# ESP01_Breakout.net
KiCad netlist of a schematic drawn in EAGLE
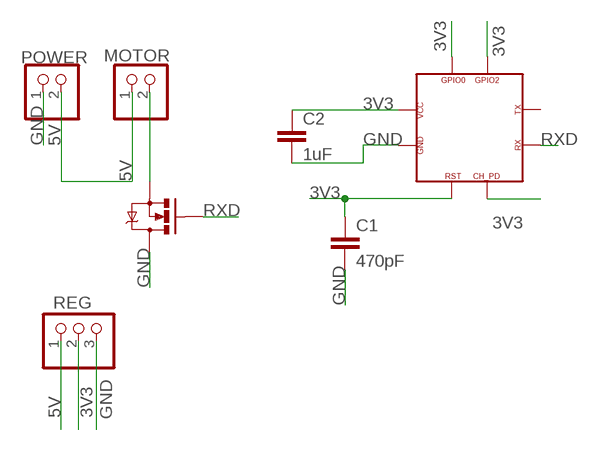
[diagram p0: schematic, sheet 1]

(export (version "E")
  (design (tool "Eeschema 10.0.6"))
  (components
    (comp (ref "C1")
      (value "470pF")
      (footprint "eagle-import:CAP-PTH-SMALLEZ")
      (libsource (lib "eagle-import") (part "CAPEZ"))
    )
    (comp (ref "C2")
      (value "1uF")
      (footprint "eagle-import:CAP-PTH-SMALLEZ")
      (libsource (lib "eagle-import") (part "CAPEZ"))
    )
    (comp (ref "MOTOR")
      (value "PINHD-1X2/90")
      (footprint "eagle-import:1X02_90")
      (libsource (lib "eagle-import") (part "PINHD-1X2/90"))
    )
    (comp (ref "POWER")
      (value "PINHD-1X2/90")
      (footprint "eagle-import:1X02_90")
      (libsource (lib "eagle-import") (part "PINHD-1X2/90"))
    )
    (comp (ref "Q1")
      (value "MOSFET-NCHANNEL2N7000")
      (footprint "eagle-import:TO-92")
      (libsource (lib "eagle-import") (part "MOSFET-NCHANNEL2N7000"))
    )
    (comp (ref "REG")
      (value "PINHD-1X3")
      (footprint "eagle-import:1X03")
      (libsource (lib "eagle-import") (part "PINHD-1X3"))
    )
    (comp (ref "U$2")
      (value "ESP-01")
      (footprint "eagle-import:ESP-01")
      (libsource (lib "eagle-import") (part "ESP-01"))
    )
  )
  (nets
    (net (code "1") (name "/3V3") (class "Default")
      (node (ref "C1") (pin "1") (pinfunction "1_1") (pintype "passive"))
      (node (ref "C2") (pin "1") (pinfunction "1_1") (pintype "passive"))
      (node (ref "REG") (pin "2") (pinfunction "2_2") (pintype "passive"))
      (node (ref "U$2") (pin "CH_PD") (pinfunction "CP_PD_CH_PD") (pintype "bidirectional"))
      (node (ref "U$2") (pin "GPIO0") (pinfunction "GPIO0_GPIO0") (pintype "bidirectional"))
      (node (ref "U$2") (pin "GPIO2") (pinfunction "GPIO2_GPIO2") (pintype "bidirectional"))
      (node (ref "U$2") (pin "RST") (pinfunction "RST_RST") (pintype "bidirectional"))
      (node (ref "U$2") (pin "VCC") (pinfunction "VCC_VCC") (pintype "bidirectional"))
    )
    (net (code "2") (name "/5V") (class "Default")
      (node (ref "MOTOR") (pin "1") (pinfunction "1_1") (pintype "passive"))
      (node (ref "POWER") (pin "2") (pinfunction "2_2") (pintype "passive"))
      (node (ref "REG") (pin "1") (pinfunction "1_1") (pintype "passive"))
    )
    (net (code "3") (name "/GND") (class "Default")
      (node (ref "C1") (pin "2") (pinfunction "2_2") (pintype "passive"))
      (node (ref "C2") (pin "2") (pinfunction "2_2") (pintype "passive"))
      (node (ref "POWER") (pin "1") (pinfunction "1_1") (pintype "passive"))
      (node (ref "Q1") (pin "3") (pinfunction "D_3") (pintype "passive"))
      (node (ref "REG") (pin "3") (pinfunction "3_3") (pintype "passive"))
      (node (ref "U$2") (pin "GND") (pinfunction "GND_GND") (pintype "bidirectional"))
    )
    (net (code "4") (name "/RXD") (class "Default")
      (node (ref "Q1") (pin "2") (pinfunction "G_2") (pintype "passive"))
      (node (ref "U$2") (pin "RXD") (pinfunction "RX_RXD") (pintype "bidirectional"))
    )
    (net (code "5") (name "Net-(Q1-S)") (class "Default")
      (node (ref "MOTOR") (pin "2") (pinfunction "2_2") (pintype "passive"))
      (node (ref "Q1") (pin "1") (pinfunction "S_1") (pintype "passive"))
    )
    (net (code "6") (name "unconnected-(U$2-TX-PadTXD)") (class "Default")
      (node (ref "U$2") (pin "TXD") (pinfunction "TX_TXD") (pintype "bidirectional"))
    )
  )
)
